# MCU_Status_LED.net
KiCad netlist of a schematic drawn in Altium Designer
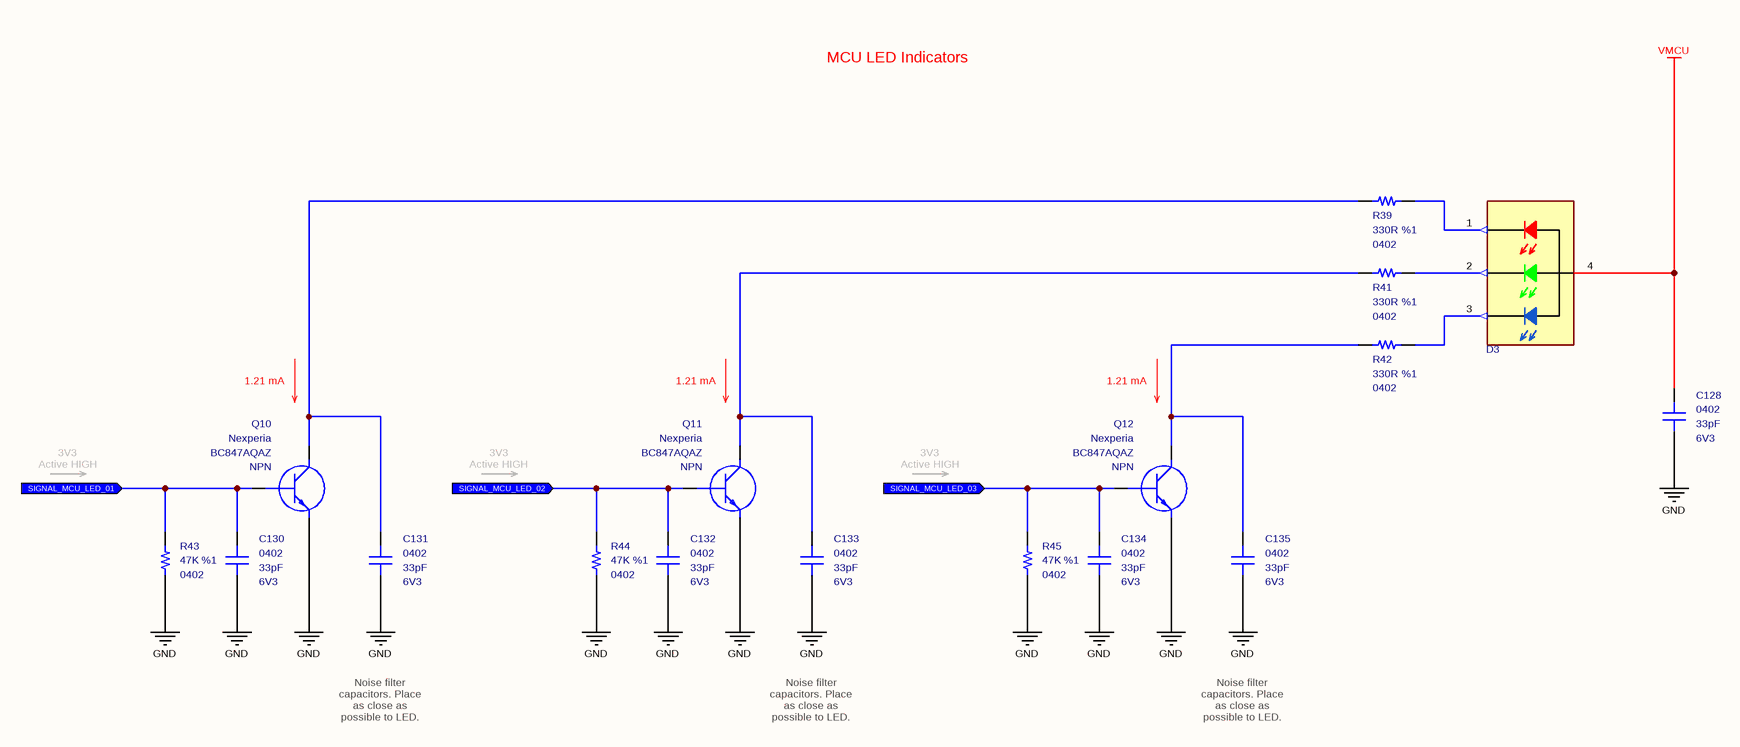
[diagram p0: MCU Status LED.SchDoc]

(export (version "E")
  (design (tool "Eeschema 10.0.6"))
  (components
    (comp (ref "C128")
      (value "33pF")
      (footprint "CAPACITOR_0402")
      (description "Capacitor - 33pF [0402] (Ceramic)")
      (fields
        (field (name "MANUFACTURER_PART_NUMBER") "C0402C330J9RACAUTO")
        (field (name "MOUSER_PART_NUMBER") "80-C0402C330J9RAUTO")
        (field (name "CASE") "0402")
        (field (name "VOLTAGE") "6V3")
      )
      (libsource (lib "Ovoo_Schematic") (part "Capacitor - 33pF [0402-6V3]"))
    )
    (comp (ref "C130")
      (value "33pF")
      (footprint "CAPACITOR_0402")
      (description "Capacitor - 33pF [0402] (Ceramic)")
      (fields
        (field (name "MANUFACTURER_PART_NUMBER") "C0402C330J9RACAUTO")
        (field (name "MOUSER_PART_NUMBER") "80-C0402C330J9RAUTO")
        (field (name "CASE") "0402")
        (field (name "VOLTAGE") "6V3")
      )
      (libsource (lib "Ovoo_Schematic") (part "Capacitor - 33pF [0402-6V3]"))
    )
    (comp (ref "C131")
      (value "33pF")
      (footprint "CAPACITOR_0402")
      (description "Capacitor - 33pF [0402] (Ceramic)")
      (fields
        (field (name "MANUFACTURER_PART_NUMBER") "C0402C330J9RACAUTO")
        (field (name "MOUSER_PART_NUMBER") "80-C0402C330J9RAUTO")
        (field (name "CASE") "0402")
        (field (name "VOLTAGE") "6V3")
      )
      (libsource (lib "Ovoo_Schematic") (part "Capacitor - 33pF [0402-6V3]"))
    )
    (comp (ref "C132")
      (value "33pF")
      (footprint "CAPACITOR_0402")
      (description "Capacitor - 33pF [0402] (Ceramic)")
      (fields
        (field (name "MANUFACTURER_PART_NUMBER") "C0402C330J9RACAUTO")
        (field (name "MOUSER_PART_NUMBER") "80-C0402C330J9RAUTO")
        (field (name "CASE") "0402")
        (field (name "VOLTAGE") "6V3")
      )
      (libsource (lib "Ovoo_Schematic") (part "Capacitor - 33pF [0402-6V3]"))
    )
    (comp (ref "C133")
      (value "33pF")
      (footprint "CAPACITOR_0402")
      (description "Capacitor - 33pF [0402] (Ceramic)")
      (fields
        (field (name "MANUFACTURER_PART_NUMBER") "C0402C330J9RACAUTO")
        (field (name "MOUSER_PART_NUMBER") "80-C0402C330J9RAUTO")
        (field (name "CASE") "0402")
        (field (name "VOLTAGE") "6V3")
      )
      (libsource (lib "Ovoo_Schematic") (part "Capacitor - 33pF [0402-6V3]"))
    )
    (comp (ref "C134")
      (value "33pF")
      (footprint "CAPACITOR_0402")
      (description "Capacitor - 33pF [0402] (Ceramic)")
      (fields
        (field (name "MANUFACTURER_PART_NUMBER") "C0402C330J9RACAUTO")
        (field (name "MOUSER_PART_NUMBER") "80-C0402C330J9RAUTO")
        (field (name "CASE") "0402")
        (field (name "VOLTAGE") "6V3")
      )
      (libsource (lib "Ovoo_Schematic") (part "Capacitor - 33pF [0402-6V3]"))
    )
    (comp (ref "C135")
      (value "33pF")
      (footprint "CAPACITOR_0402")
      (description "Capacitor - 33pF [0402] (Ceramic)")
      (fields
        (field (name "MANUFACTURER_PART_NUMBER") "C0402C330J9RACAUTO")
        (field (name "MOUSER_PART_NUMBER") "80-C0402C330J9RAUTO")
        (field (name "CASE") "0402")
        (field (name "VOLTAGE") "6V3")
      )
      (libsource (lib "Ovoo_Schematic") (part "Capacitor - 33pF [0402-6V3]"))
    )
    (comp (ref "D3")
      (value "150066M153000")
      (footprint "Wurth_0606")
      (description "Standard LEDs - SMD PICOLED series Red LED")
      (fields (field (name "MOUSER PART NUMBER") "710-150066M153000"))
      (libsource (lib "Ovoo_Library") (part "Diode - RGB LED (150066M153000)"))
    )
    (comp (ref "Q10")
      (value "Bipolar NPN Transistors")
      (footprint "SOT1215")
      (description "Bipolar Transistors - BJT BC847AQA/DFN1010D-3/REEL 7\" Q2")
      (fields
        (field (name "MOUSER_PART_NUMBER") "771-BC847AQAZ")
        (field (name "MANUFACTURER_NAME") "Nexperia")
        (field (name "MANUFACTURER_PART_NUMBER") "BC847AQAZ")
        (field (name "POLARITY") "NPN")
      )
      (libsource (lib "Ovoo_Schematic") (part "Transistor - BC847"))
    )
    (comp (ref "Q11")
      (value "Bipolar NPN Transistors")
      (footprint "SOT1215")
      (description "Bipolar Transistors - BJT BC847AQA/DFN1010D-3/REEL 7\" Q2")
      (fields
        (field (name "MOUSER_PART_NUMBER") "771-BC847AQAZ")
        (field (name "MANUFACTURER_NAME") "Nexperia")
        (field (name "MANUFACTURER_PART_NUMBER") "BC847AQAZ")
        (field (name "POLARITY") "NPN")
      )
      (libsource (lib "Ovoo_Schematic") (part "Transistor - BC847"))
    )
    (comp (ref "Q12")
      (value "Bipolar NPN Transistors")
      (footprint "SOT1215")
      (description "Bipolar Transistors - BJT BC847AQA/DFN1010D-3/REEL 7\" Q2")
      (fields
        (field (name "MOUSER_PART_NUMBER") "771-BC847AQAZ")
        (field (name "MANUFACTURER_NAME") "Nexperia")
        (field (name "MANUFACTURER_PART_NUMBER") "BC847AQAZ")
        (field (name "POLARITY") "NPN")
      )
      (libsource (lib "Ovoo_Schematic") (part "Transistor - BC847"))
    )
    (comp (ref "R39")
      (value "330R")
      (footprint "RESISTOR_0402")
      (description "Thick Film Resistors - SMD 1/16 W 330 Ohm 1%")
      (fields
        (field (name "MANUFACTURER_PART_NUMBER") "CRCW0402330RFKED")
        (field (name "MOUSER_PART_NUMBER") "71-CRCW0402-330-E3")
        (field (name "TOLERANCE") "%1")
        (field (name "CASE") "0402")
      )
      (libsource (lib "Ovoo_Schematic") (part "Resistor - 330R"))
    )
    (comp (ref "R41")
      (value "330R")
      (footprint "RESISTOR_0402")
      (description "Thick Film Resistors - SMD 1/16 W 330 Ohm 1%")
      (fields
        (field (name "MANUFACTURER_PART_NUMBER") "CRCW0402330RFKED")
        (field (name "MOUSER_PART_NUMBER") "71-CRCW0402-330-E3")
        (field (name "TOLERANCE") "%1")
        (field (name "CASE") "0402")
      )
      (libsource (lib "Ovoo_Schematic") (part "Resistor - 330R"))
    )
    (comp (ref "R42")
      (value "330R")
      (footprint "RESISTOR_0402")
      (description "Thick Film Resistors - SMD 1/16 W 330 Ohm 1%")
      (fields
        (field (name "MANUFACTURER_PART_NUMBER") "CRCW0402330RFKED")
        (field (name "MOUSER_PART_NUMBER") "71-CRCW0402-330-E3")
        (field (name "TOLERANCE") "%1")
        (field (name "CASE") "0402")
      )
      (libsource (lib "Ovoo_Schematic") (part "Resistor - 330R"))
    )
    (comp (ref "R43")
      (value "47K")
      (footprint "RESISTOR_0402")
      (description "Thick Film Resistors - SMD 1/16 W 47 Kohms 1%")
      (fields
        (field (name "MANUFACTURER_PART_NUMBER") "CRCW040247K0FKED")
        (field (name "MOUSER_PART_NUMBER") "71-CRCW0402-47K-E3")
        (field (name "TOLERANCE") "%1")
        (field (name "CASE") "0402")
      )
      (libsource (lib "Ovoo_Schematic") (part "Resistor - 47K"))
    )
    (comp (ref "R44")
      (value "47K")
      (footprint "RESISTOR_0402")
      (description "Thick Film Resistors - SMD 1/16 W 47 Kohms 1%")
      (fields
        (field (name "MANUFACTURER_PART_NUMBER") "CRCW040247K0FKED")
        (field (name "MOUSER_PART_NUMBER") "71-CRCW0402-47K-E3")
        (field (name "TOLERANCE") "%1")
        (field (name "CASE") "0402")
      )
      (libsource (lib "Ovoo_Schematic") (part "Resistor - 47K"))
    )
    (comp (ref "R45")
      (value "47K")
      (footprint "RESISTOR_0402")
      (description "Thick Film Resistors - SMD 1/16 W 47 Kohms 1%")
      (fields
        (field (name "MANUFACTURER_PART_NUMBER") "CRCW040247K0FKED")
        (field (name "MOUSER_PART_NUMBER") "71-CRCW0402-47K-E3")
        (field (name "TOLERANCE") "%1")
        (field (name "CASE") "0402")
      )
      (libsource (lib "Ovoo_Schematic") (part "Resistor - 47K"))
    )
  )
  (nets
    (net (code "1") (name "/SIGNAL_MCU_LED_01") (class "Default")
      (node (ref "C130") (pin "1") (pinfunction "1_1") (pintype "passive"))
      (node (ref "Q10") (pin "1") (pinfunction "B_1") (pintype "passive"))
      (node (ref "R43") (pin "2") (pinfunction "2_2") (pintype "passive"))
    )
    (net (code "2") (name "/SIGNAL_MCU_LED_02") (class "Default")
      (node (ref "C132") (pin "1") (pinfunction "1_1") (pintype "passive"))
      (node (ref "Q11") (pin "1") (pinfunction "B_1") (pintype "passive"))
      (node (ref "R44") (pin "2") (pinfunction "2_2") (pintype "passive"))
    )
    (net (code "3") (name "/SIGNAL_MCU_LED_03") (class "Default")
      (node (ref "C134") (pin "1") (pinfunction "1_1") (pintype "passive"))
      (node (ref "Q12") (pin "1") (pinfunction "B_1") (pintype "passive"))
      (node (ref "R45") (pin "2") (pinfunction "2_2") (pintype "passive"))
    )
    (net (code "4") (name "GND") (class "Default")
      (node (ref "C128") (pin "2") (pinfunction "2_2") (pintype "passive"))
      (node (ref "C130") (pin "2") (pinfunction "2_2") (pintype "passive"))
      (node (ref "C131") (pin "2") (pinfunction "2_2") (pintype "passive"))
      (node (ref "C132") (pin "2") (pinfunction "2_2") (pintype "passive"))
      (node (ref "C133") (pin "2") (pinfunction "2_2") (pintype "passive"))
      (node (ref "C134") (pin "2") (pinfunction "2_2") (pintype "passive"))
      (node (ref "C135") (pin "2") (pinfunction "2_2") (pintype "passive"))
      (node (ref "Q10") (pin "2") (pinfunction "E_2") (pintype "passive"))
      (node (ref "Q11") (pin "2") (pinfunction "E_2") (pintype "passive"))
      (node (ref "Q12") (pin "2") (pinfunction "E_2") (pintype "passive"))
      (node (ref "R43") (pin "1") (pinfunction "1_1") (pintype "passive"))
      (node (ref "R44") (pin "1") (pinfunction "1_1") (pintype "passive"))
      (node (ref "R45") (pin "1") (pinfunction "1_1") (pintype "passive"))
    )
    (net (code "5") (name "Net-(D3-Pad1)") (class "Default")
      (node (ref "D3") (pin "1") (pinfunction "1_1") (pintype "output"))
      (node (ref "R39") (pin "2") (pinfunction "2_2") (pintype "passive"))
    )
    (net (code "6") (name "Net-(D3-Pad2)") (class "Default")
      (node (ref "D3") (pin "2") (pinfunction "2_2") (pintype "output"))
      (node (ref "R41") (pin "2") (pinfunction "2_2") (pintype "passive"))
    )
    (net (code "7") (name "Net-(D3-Pad3)") (class "Default")
      (node (ref "D3") (pin "3") (pinfunction "3_3") (pintype "output"))
      (node (ref "R42") (pin "2") (pinfunction "2_2") (pintype "passive"))
    )
    (net (code "8") (name "Net-(Q10-C)") (class "Default")
      (node (ref "C131") (pin "1") (pinfunction "1_1") (pintype "passive"))
      (node (ref "Q10") (pin "3") (pinfunction "C_3") (pintype "passive"))
      (node (ref "R39") (pin "1") (pinfunction "1_1") (pintype "passive"))
    )
    (net (code "9") (name "Net-(Q11-C)") (class "Default")
      (node (ref "C133") (pin "1") (pinfunction "1_1") (pintype "passive"))
      (node (ref "Q11") (pin "3") (pinfunction "C_3") (pintype "passive"))
      (node (ref "R41") (pin "1") (pinfunction "1_1") (pintype "passive"))
    )
    (net (code "10") (name "Net-(Q12-C)") (class "Default")
      (node (ref "C135") (pin "1") (pinfunction "1_1") (pintype "passive"))
      (node (ref "Q12") (pin "3") (pinfunction "C_3") (pintype "passive"))
      (node (ref "R42") (pin "1") (pinfunction "1_1") (pintype "passive"))
    )
    (net (code "11") (name "VMCU") (class "Default")
      (node (ref "C128") (pin "1") (pinfunction "1_1") (pintype "passive"))
      (node (ref "D3") (pin "4") (pinfunction "4_4") (pintype "power_in"))
    )
  )
)
